# Channel_B.net
KiCad netlist of a schematic drawn in Altium Designer
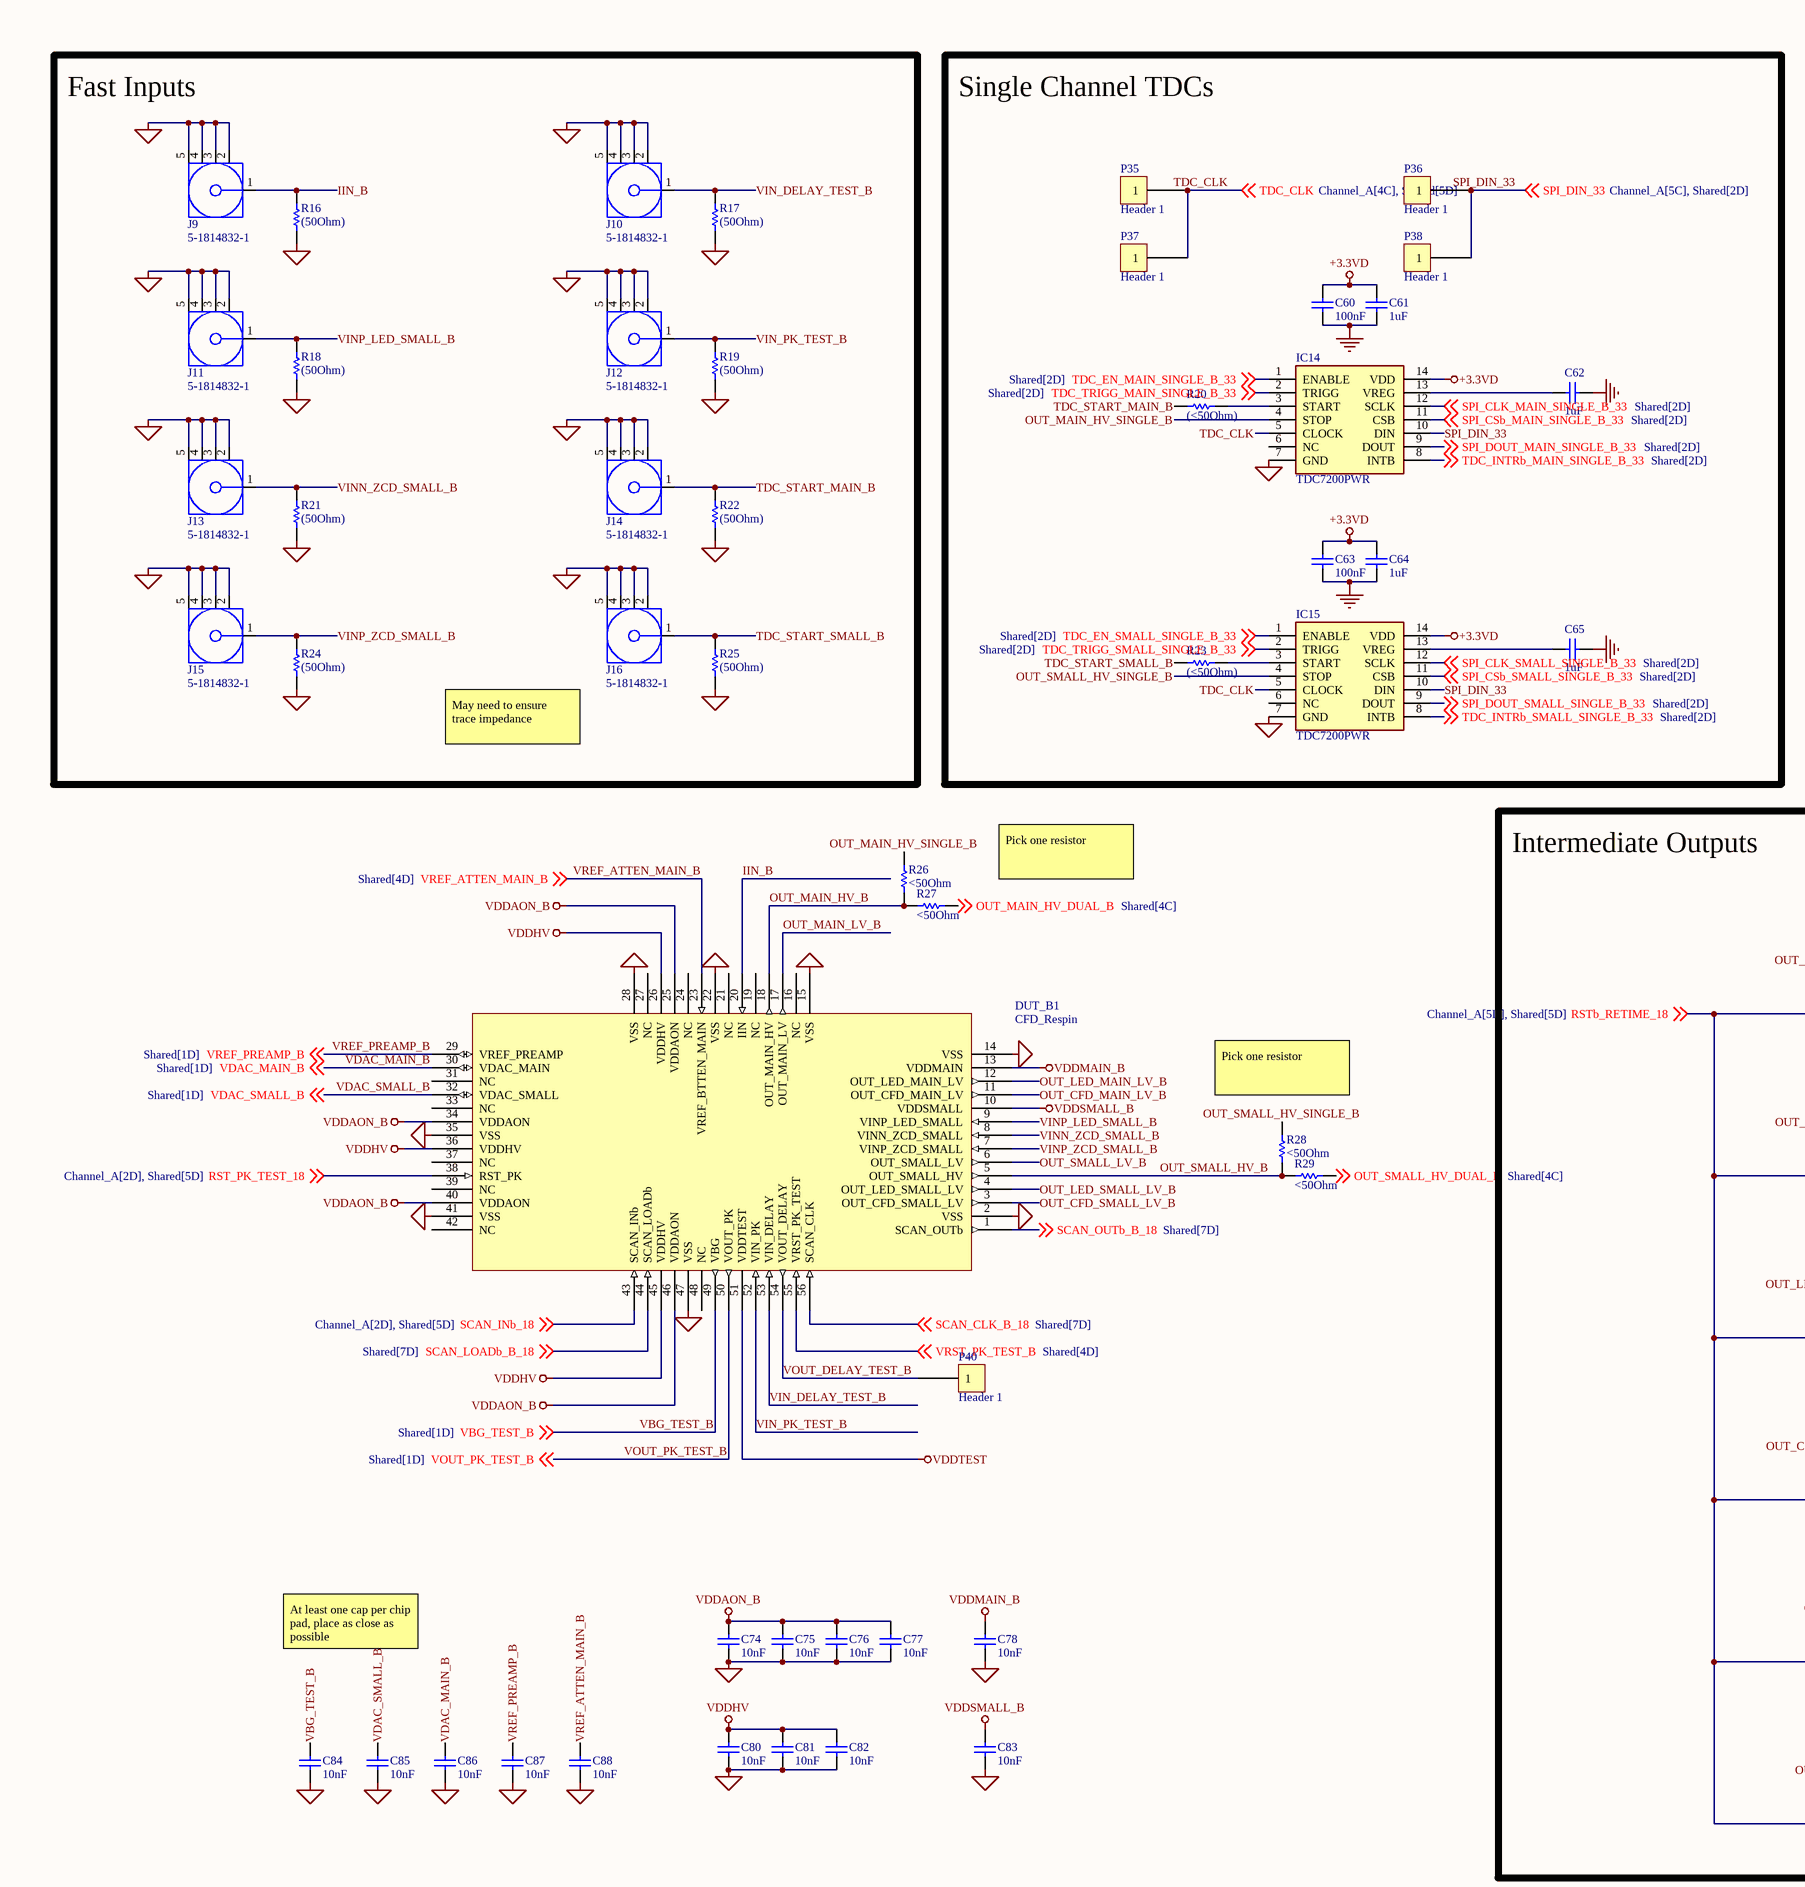
[diagram p0: Channel_B.SchDoc, left]
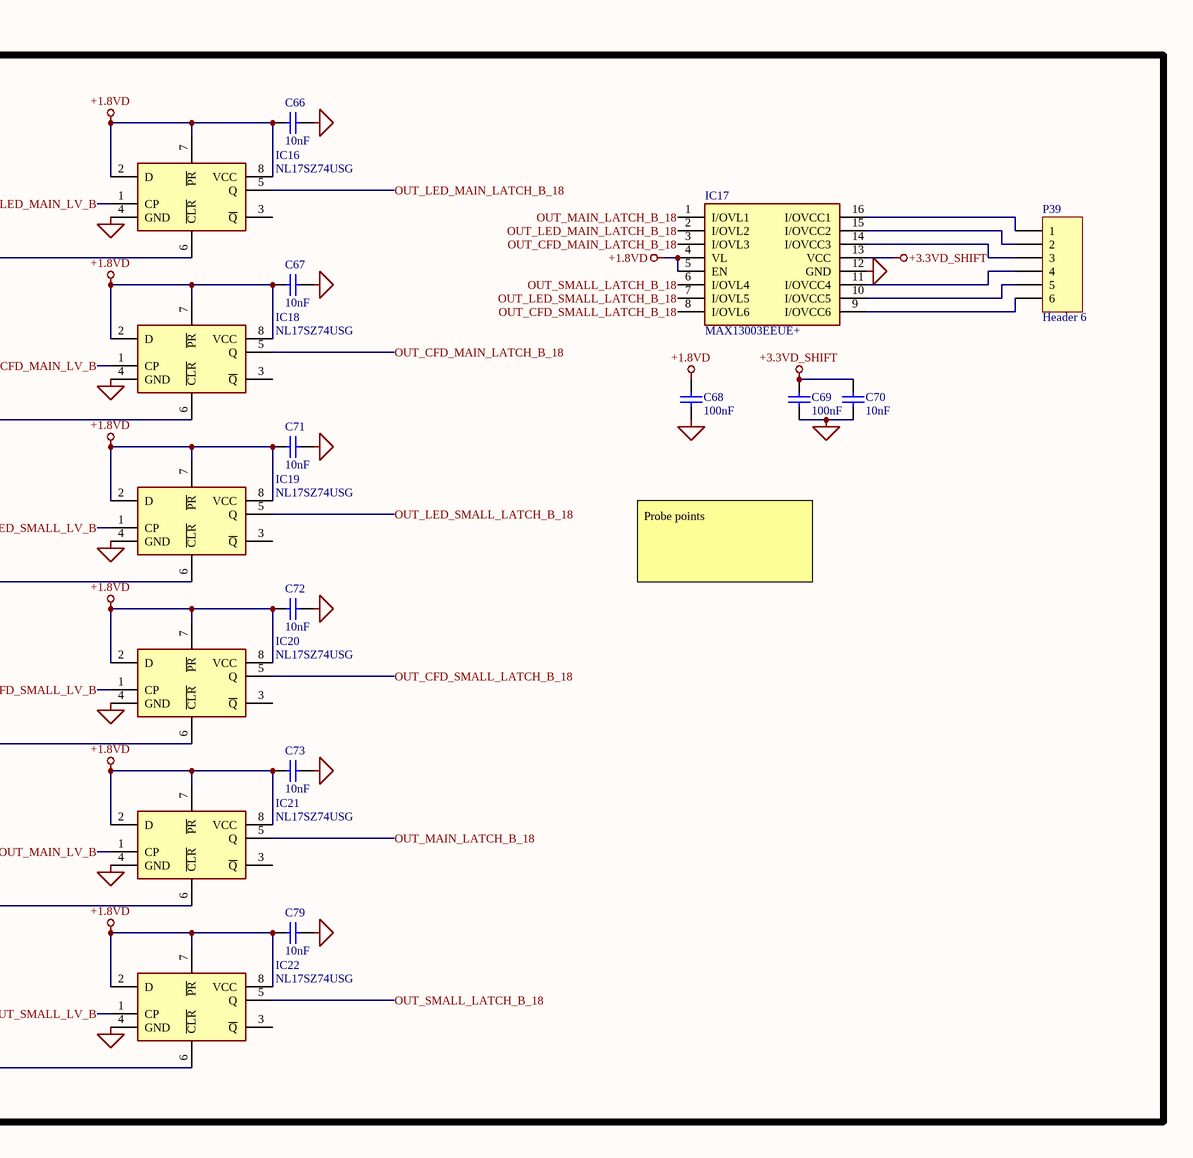
[diagram p1: Channel_B.SchDoc, right]

(export (version "E")
  (design (tool "Eeschema 10.0.6"))
  (components
    (comp (ref "C60")
      (value "100nF")
      (footprint "CAPC1608X90X35ML10T15")
      (description "0603")
      (fields (field (name "MANUFACTURER") "Murata"))
      (libsource (lib "Altium Content Vault") (part "CAP-NP-2"))
    )
    (comp (ref "C61")
      (value "1uF")
      (footprint "CAPC1608X90X35ML10T15")
      (description "0603")
      (fields (field (name "MANUFACTURER") "Murata"))
      (libsource (lib "Altium Content Vault") (part "CAP-NP-2"))
    )
    (comp (ref "C62")
      (value "1uF")
      (footprint "CAPC1608X90X35ML10T15")
      (description "0603")
      (fields (field (name "MANUFACTURER") "Murata"))
      (libsource (lib "Altium Content Vault") (part "CAP-NP-2"))
    )
    (comp (ref "C63")
      (value "100nF")
      (footprint "CAPC1608X90X35ML10T15")
      (description "0603")
      (fields (field (name "MANUFACTURER") "Murata"))
      (libsource (lib "Altium Content Vault") (part "CAP-NP-2"))
    )
    (comp (ref "C64")
      (value "1uF")
      (footprint "CAPC1608X90X35ML10T15")
      (description "0603")
      (fields (field (name "MANUFACTURER") "Murata"))
      (libsource (lib "Altium Content Vault") (part "CAP-NP-2"))
    )
    (comp (ref "C65")
      (value "1uF")
      (footprint "CAPC1608X90X35ML10T15")
      (description "0603")
      (fields (field (name "MANUFACTURER") "Murata"))
      (libsource (lib "Altium Content Vault") (part "CAP-NP-2"))
    )
    (comp (ref "C66")
      (value "10nF")
      (footprint "CAPC1608X90X35ML10T15")
      (description "0603")
      (fields (field (name "MANUFACTURER") "Murata"))
      (libsource (lib "Altium Content Vault") (part "CAP-NP-2"))
    )
    (comp (ref "C67")
      (value "10nF")
      (footprint "CAPC1608X90X35ML10T15")
      (description "0603")
      (fields (field (name "MANUFACTURER") "Murata"))
      (libsource (lib "Altium Content Vault") (part "CAP-NP-2"))
    )
    (comp (ref "C68")
      (value "100nF")
      (footprint "CAPC1608X90X35ML10T15")
      (description "0603")
      (fields (field (name "MANUFACTURER") "Murata"))
      (libsource (lib "Altium Content Vault") (part "CAP-NP-2"))
    )
    (comp (ref "C69")
      (value "100nF")
      (footprint "CAPC1608X90X35ML10T15")
      (description "0603")
      (fields (field (name "MANUFACTURER") "Murata"))
      (libsource (lib "Altium Content Vault") (part "CAP-NP-2"))
    )
    (comp (ref "C70")
      (value "10nF")
      (footprint "CAPC1608X90X35ML10T15")
      (description "0603")
      (fields (field (name "MANUFACTURER") "Murata"))
      (libsource (lib "Altium Content Vault") (part "CAP-NP-2"))
    )
    (comp (ref "C71")
      (value "10nF")
      (footprint "CAPC1608X90X35ML10T15")
      (description "0603")
      (fields (field (name "MANUFACTURER") "Murata"))
      (libsource (lib "Altium Content Vault") (part "CAP-NP-2"))
    )
    (comp (ref "C72")
      (value "10nF")
      (footprint "CAPC1608X90X35ML10T15")
      (description "0603")
      (fields (field (name "MANUFACTURER") "Murata"))
      (libsource (lib "Altium Content Vault") (part "CAP-NP-2"))
    )
    (comp (ref "C73")
      (value "10nF")
      (footprint "CAPC1608X90X35ML10T15")
      (description "0603")
      (fields (field (name "MANUFACTURER") "Murata"))
      (libsource (lib "Altium Content Vault") (part "CAP-NP-2"))
    )
    (comp (ref "C74")
      (value "10nF")
      (footprint "CAPC1608X90X35ML10T15")
      (description "0603")
      (fields (field (name "MANUFACTURER") "Murata"))
      (libsource (lib "Altium Content Vault") (part "CAP-NP-2"))
    )
    (comp (ref "C75")
      (value "10nF")
      (footprint "CAPC1608X90X35ML10T15")
      (description "0603")
      (fields (field (name "MANUFACTURER") "Murata"))
      (libsource (lib "Altium Content Vault") (part "CAP-NP-2"))
    )
    (comp (ref "C76")
      (value "10nF")
      (footprint "CAPC1608X90X35ML10T15")
      (description "0603")
      (fields (field (name "MANUFACTURER") "Murata"))
      (libsource (lib "Altium Content Vault") (part "CAP-NP-2"))
    )
    (comp (ref "C77")
      (value "10nF")
      (footprint "CAPC1608X90X35ML10T15")
      (description "0603")
      (fields (field (name "MANUFACTURER") "Murata"))
      (libsource (lib "Altium Content Vault") (part "CAP-NP-2"))
    )
    (comp (ref "C78")
      (value "10nF")
      (footprint "CAPC1608X90X35ML10T15")
      (description "0603")
      (fields (field (name "MANUFACTURER") "Murata"))
      (libsource (lib "Altium Content Vault") (part "CAP-NP-2"))
    )
    (comp (ref "C79")
      (value "10nF")
      (footprint "CAPC1608X90X35ML10T15")
      (description "0603")
      (fields (field (name "MANUFACTURER") "Murata"))
      (libsource (lib "Altium Content Vault") (part "CAP-NP-2"))
    )
    (comp (ref "C80")
      (value "10nF")
      (footprint "CAPC1608X90X35ML10T15")
      (description "0603")
      (fields (field (name "MANUFACTURER") "Murata"))
      (libsource (lib "Altium Content Vault") (part "CAP-NP-2"))
    )
    (comp (ref "C81")
      (value "10nF")
      (footprint "CAPC1608X90X35ML10T15")
      (description "0603")
      (fields (field (name "MANUFACTURER") "Murata"))
      (libsource (lib "Altium Content Vault") (part "CAP-NP-2"))
    )
    (comp (ref "C82")
      (value "10nF")
      (footprint "CAPC1608X90X35ML10T15")
      (description "0603")
      (fields (field (name "MANUFACTURER") "Murata"))
      (libsource (lib "Altium Content Vault") (part "CAP-NP-2"))
    )
    (comp (ref "C83")
      (value "10nF")
      (footprint "CAPC1608X90X35ML10T15")
      (description "0603")
      (fields (field (name "MANUFACTURER") "Murata"))
      (libsource (lib "Altium Content Vault") (part "CAP-NP-2"))
    )
    (comp (ref "C84")
      (value "10nF")
      (footprint "CAPC1608X90X35ML10T15")
      (description "0603")
      (fields (field (name "MANUFACTURER") "Murata"))
      (libsource (lib "Altium Content Vault") (part "CAP-NP-2"))
    )
    (comp (ref "C85")
      (value "10nF")
      (footprint "CAPC1608X90X35ML10T15")
      (description "0603")
      (fields (field (name "MANUFACTURER") "Murata"))
      (libsource (lib "Altium Content Vault") (part "CAP-NP-2"))
    )
    (comp (ref "C86")
      (value "10nF")
      (footprint "CAPC1608X90X35ML10T15")
      (description "0603")
      (fields (field (name "MANUFACTURER") "Murata"))
      (libsource (lib "Altium Content Vault") (part "CAP-NP-2"))
    )
    (comp (ref "C87")
      (value "10nF")
      (footprint "CAPC1608X90X35ML10T15")
      (description "0603")
      (fields (field (name "MANUFACTURER") "Murata"))
      (libsource (lib "Altium Content Vault") (part "CAP-NP-2"))
    )
    (comp (ref "C88")
      (value "10nF")
      (footprint "CAPC1608X90X35ML10T15")
      (description "0603")
      (fields (field (name "MANUFACTURER") "Murata"))
      (libsource (lib "Altium Content Vault") (part "CAP-NP-2"))
    )
    (comp (ref "DUT_B1")
      (value "CFD_Respin")
      (footprint "QFN50P800X800X80_HS-57N_WIDEVIAS")
      (libsource (lib "intlib") (part "CFD_Respin"))
    )
    (comp (ref "IC14")
      (value "TDC7200PWR")
      (footprint "SamacSys:SOP65P640X120-14N")
      (description "Integrated Circuit")
      (libsource (lib "*") (part "TDC7200PWR"))
    )
    (comp (ref "IC15")
      (value "TDC7200PWR")
      (footprint "SamacSys:SOP65P640X120-14N")
      (description "Integrated Circuit")
      (libsource (lib "*") (part "TDC7200PWR"))
    )
    (comp (ref "IC16")
      (value "NL17SZ74USG")
      (footprint "SamacSys:SOP50P310X90-8N")
      (description "Flip Flops 1.65-5.5V CMOS Single D-Type")
      (libsource (lib "SamacSys") (part "NL17SZ74USG"))
    )
    (comp (ref "IC17")
      (value "MAX13003EEUE+")
      (footprint "SamacSys:SOP65P640X110-16N")
      (description "Integrated Circuit")
      (libsource (lib "*") (part "MAX13003EEUE+"))
    )
    (comp (ref "IC18")
      (value "NL17SZ74USG")
      (footprint "SamacSys:SOP50P310X90-8N")
      (description "Flip Flops 1.65-5.5V CMOS Single D-Type")
      (libsource (lib "SamacSys") (part "NL17SZ74USG"))
    )
    (comp (ref "IC19")
      (value "NL17SZ74USG")
      (footprint "SamacSys:SOP50P310X90-8N")
      (description "Flip Flops 1.65-5.5V CMOS Single D-Type")
      (libsource (lib "SamacSys") (part "NL17SZ74USG"))
    )
    (comp (ref "IC20")
      (value "NL17SZ74USG")
      (footprint "SamacSys:SOP50P310X90-8N")
      (description "Flip Flops 1.65-5.5V CMOS Single D-Type")
      (libsource (lib "SamacSys") (part "NL17SZ74USG"))
    )
    (comp (ref "IC21")
      (value "NL17SZ74USG")
      (footprint "SamacSys:SOP50P310X90-8N")
      (description "Flip Flops 1.65-5.5V CMOS Single D-Type")
      (libsource (lib "SamacSys") (part "NL17SZ74USG"))
    )
    (comp (ref "IC22")
      (value "NL17SZ74USG")
      (footprint "SamacSys:SOP50P310X90-8N")
      (description "Flip Flops 1.65-5.5V CMOS Single D-Type")
      (libsource (lib "SamacSys") (part "NL17SZ74USG"))
    )
    (comp (ref "J9")
      (value "5-1814832-1")
      (footprint "TECO-5-1814832-1_V")
      (fields (field (name "MANUFACTURER") "TE Connectivity"))
      (libsource (lib "Altium Content Vault") (part "CN-S-4F-RF5"))
    )
    (comp (ref "J10")
      (value "5-1814832-1")
      (footprint "TECO-5-1814832-1_V")
      (fields (field (name "MANUFACTURER") "TE Connectivity"))
      (libsource (lib "Altium Content Vault") (part "CN-S-4F-RF5"))
    )
    (comp (ref "J11")
      (value "5-1814832-1")
      (footprint "TECO-5-1814832-1_V")
      (fields (field (name "MANUFACTURER") "TE Connectivity"))
      (libsource (lib "Altium Content Vault") (part "CN-S-4F-RF5"))
    )
    (comp (ref "J12")
      (value "5-1814832-1")
      (footprint "TECO-5-1814832-1_V")
      (fields (field (name "MANUFACTURER") "TE Connectivity"))
      (libsource (lib "Altium Content Vault") (part "CN-S-4F-RF5"))
    )
    (comp (ref "J13")
      (value "5-1814832-1")
      (footprint "TECO-5-1814832-1_V")
      (fields (field (name "MANUFACTURER") "TE Connectivity"))
      (libsource (lib "Altium Content Vault") (part "CN-S-4F-RF5"))
    )
    (comp (ref "J14")
      (value "5-1814832-1")
      (footprint "TECO-5-1814832-1_V")
      (fields (field (name "MANUFACTURER") "TE Connectivity"))
      (libsource (lib "Altium Content Vault") (part "CN-S-4F-RF5"))
    )
    (comp (ref "J15")
      (value "5-1814832-1")
      (footprint "TECO-5-1814832-1_V")
      (fields (field (name "MANUFACTURER") "TE Connectivity"))
      (libsource (lib "Altium Content Vault") (part "CN-S-4F-RF5"))
    )
    (comp (ref "J16")
      (value "5-1814832-1")
      (footprint "TECO-5-1814832-1_V")
      (fields (field (name "MANUFACTURER") "TE Connectivity"))
      (libsource (lib "Altium Content Vault") (part "CN-S-4F-RF5"))
    )
    (comp (ref "P35") (value "Header 1") (footprint "Header1") (libsource (lib "intlib") (part "Header 1")))
    (comp (ref "P36") (value "Header 1") (footprint "Header1") (libsource (lib "intlib") (part "Header 1")))
    (comp (ref "P37") (value "Header 1") (footprint "Header1") (libsource (lib "intlib") (part "Header 1")))
    (comp (ref "P38") (value "Header 1") (footprint "Header1") (libsource (lib "intlib") (part "Header 1")))
    (comp (ref "P39")
      (value "Header 6")
      (footprint "HDR1X6")
      (description "Header, 6-Pin")
      (fields (field (name "PUBLISHER") "Altium Limited"))
      (libsource (lib "Miscellaneous Connectors") (part "Header 6"))
    )
    (comp (ref "P40") (value "Header 1") (footprint "Header1") (libsource (lib "") (part "Header 1_1")))
    (comp (ref "R16")
      (value "(50Ohm)")
      (footprint "RESC1609X50X30NL8T20")
      (description "0603")
      (fields (field (name "MANUFACTURER") "Vishay Semiconductor"))
      (libsource (lib "Altium Content Vault") (part "RES-2"))
    )
    (comp (ref "R17")
      (value "(50Ohm)")
      (footprint "RESC1609X50X30NL8T20")
      (description "0603")
      (fields (field (name "MANUFACTURER") "Vishay Semiconductor"))
      (libsource (lib "Altium Content Vault") (part "RES-2"))
    )
    (comp (ref "R18")
      (value "(50Ohm)")
      (footprint "RESC1609X50X30NL8T20")
      (description "0603")
      (fields (field (name "MANUFACTURER") "Vishay Semiconductor"))
      (libsource (lib "Altium Content Vault") (part "RES-2"))
    )
    (comp (ref "R19")
      (value "(50Ohm)")
      (footprint "RESC1609X50X30NL8T20")
      (description "0603")
      (fields (field (name "MANUFACTURER") "Vishay Semiconductor"))
      (libsource (lib "Altium Content Vault") (part "RES-2"))
    )
    (comp (ref "R20")
      (value "(<50Ohm)")
      (footprint "RESC1609X50X30NL8T20")
      (description "0603")
      (fields (field (name "MANUFACTURER") "Vishay Semiconductor"))
      (libsource (lib "Altium Content Vault") (part "RES-2"))
    )
    (comp (ref "R21")
      (value "(50Ohm)")
      (footprint "RESC1609X50X30NL8T20")
      (description "0603")
      (fields (field (name "MANUFACTURER") "Vishay Semiconductor"))
      (libsource (lib "Altium Content Vault") (part "RES-2"))
    )
    (comp (ref "R22")
      (value "(50Ohm)")
      (footprint "RESC1609X50X30NL8T20")
      (description "0603")
      (fields (field (name "MANUFACTURER") "Vishay Semiconductor"))
      (libsource (lib "Altium Content Vault") (part "RES-2"))
    )
    (comp (ref "R23")
      (value "(<50Ohm)")
      (footprint "RESC1609X50X30NL8T20")
      (description "0603")
      (fields (field (name "MANUFACTURER") "Vishay Semiconductor"))
      (libsource (lib "Altium Content Vault") (part "RES-2"))
    )
    (comp (ref "R24")
      (value "(50Ohm)")
      (footprint "RESC1609X50X30NL8T20")
      (description "0603")
      (fields (field (name "MANUFACTURER") "Vishay Semiconductor"))
      (libsource (lib "Altium Content Vault") (part "RES-2"))
    )
    (comp (ref "R25")
      (value "(50Ohm)")
      (footprint "RESC1609X50X30NL8T20")
      (description "0603")
      (fields (field (name "MANUFACTURER") "Vishay Semiconductor"))
      (libsource (lib "Altium Content Vault") (part "RES-2"))
    )
    (comp (ref "R26")
      (value "<50Ohm")
      (footprint "RESC1609X50X30NL8T20")
      (description "0603")
      (fields (field (name "MANUFACTURER") "Vishay Semiconductor"))
      (libsource (lib "Altium Content Vault") (part "RES-2"))
    )
    (comp (ref "R27")
      (value "<50Ohm")
      (footprint "RESC1609X50X30NL8T20")
      (description "0603")
      (fields (field (name "MANUFACTURER") "Vishay Semiconductor"))
      (libsource (lib "Altium Content Vault") (part "RES-2"))
    )
    (comp (ref "R28")
      (value "<50Ohm")
      (footprint "RESC1609X50X30NL8T20")
      (description "0603")
      (fields (field (name "MANUFACTURER") "Vishay Semiconductor"))
      (libsource (lib "Altium Content Vault") (part "RES-2"))
    )
    (comp (ref "R29")
      (value "<50Ohm")
      (footprint "RESC1609X50X30NL8T20")
      (description "0603")
      (fields (field (name "MANUFACTURER") "Vishay Semiconductor"))
      (libsource (lib "Altium Content Vault") (part "RES-2"))
    )
  )
  (nets
    (net (code "1") (name "+1.8VD") (class "Default")
      (node (ref "C66") (pin "2") (pinfunction "2_2") (pintype "passive"))
      (node (ref "C67") (pin "2") (pinfunction "2_2") (pintype "passive"))
      (node (ref "C68") (pin "2") (pinfunction "2_2") (pintype "passive"))
      (node (ref "C71") (pin "2") (pinfunction "2_2") (pintype "passive"))
      (node (ref "C72") (pin "2") (pinfunction "2_2") (pintype "passive"))
      (node (ref "C73") (pin "2") (pinfunction "2_2") (pintype "passive"))
      (node (ref "C79") (pin "2") (pinfunction "2_2") (pintype "passive"))
      (node (ref "IC16") (pin "2") (pinfunction "D_2") (pintype "passive"))
      (node (ref "IC16") (pin "7") (pinfunction "~{PR}_7") (pintype "passive"))
      (node (ref "IC16") (pin "8") (pinfunction "VCC_8") (pintype "passive"))
      (node (ref "IC17") (pin "4") (pinfunction "VL_4") (pintype "passive"))
      (node (ref "IC17") (pin "5") (pinfunction "EN_5") (pintype "passive"))
      (node (ref "IC18") (pin "2") (pinfunction "D_2") (pintype "passive"))
      (node (ref "IC18") (pin "7") (pinfunction "~{PR}_7") (pintype "passive"))
      (node (ref "IC18") (pin "8") (pinfunction "VCC_8") (pintype "passive"))
      (node (ref "IC19") (pin "2") (pinfunction "D_2") (pintype "passive"))
      (node (ref "IC19") (pin "7") (pinfunction "~{PR}_7") (pintype "passive"))
      (node (ref "IC19") (pin "8") (pinfunction "VCC_8") (pintype "passive"))
      (node (ref "IC20") (pin "2") (pinfunction "D_2") (pintype "passive"))
      (node (ref "IC20") (pin "7") (pinfunction "~{PR}_7") (pintype "passive"))
      (node (ref "IC20") (pin "8") (pinfunction "VCC_8") (pintype "passive"))
      (node (ref "IC21") (pin "2") (pinfunction "D_2") (pintype "passive"))
      (node (ref "IC21") (pin "7") (pinfunction "~{PR}_7") (pintype "passive"))
      (node (ref "IC21") (pin "8") (pinfunction "VCC_8") (pintype "passive"))
      (node (ref "IC22") (pin "2") (pinfunction "D_2") (pintype "passive"))
      (node (ref "IC22") (pin "7") (pinfunction "~{PR}_7") (pintype "passive"))
      (node (ref "IC22") (pin "8") (pinfunction "VCC_8") (pintype "passive"))
    )
    (net (code "2") (name "+3.3VD") (class "Default")
      (node (ref "C60") (pin "1") (pinfunction "1_1") (pintype "passive"))
      (node (ref "C61") (pin "1") (pinfunction "1_1") (pintype "passive"))
      (node (ref "C63") (pin "1") (pinfunction "1_1") (pintype "passive"))
      (node (ref "C64") (pin "1") (pinfunction "1_1") (pintype "passive"))
      (node (ref "IC14") (pin "14") (pinfunction "VDD_14") (pintype "passive"))
      (node (ref "IC15") (pin "14") (pinfunction "VDD_14") (pintype "passive"))
    )
    (net (code "3") (name "+3.3VD_SHIFT") (class "Default")
      (node (ref "C69") (pin "2") (pinfunction "2_2") (pintype "passive"))
      (node (ref "C70") (pin "2") (pinfunction "2_2") (pintype "passive"))
      (node (ref "IC17") (pin "13") (pinfunction "VCC_13") (pintype "passive"))
    )
    (net (code "4") (name "/IIN_B") (class "Default")
      (node (ref "DUT_B1") (pin "20") (pinfunction "IIN_20") (pintype "input"))
      (node (ref "J9") (pin "1") (pinfunction "1_1") (pintype "passive"))
      (node (ref "R16") (pin "2") (pinfunction "2_2") (pintype "passive"))
    )
    (net (code "5") (name "/OUT_CFD_MAIN_LATCH_B_18") (class "Default")
      (node (ref "IC17") (pin "3") (pinfunction "I/OVL3_3") (pintype "passive"))
      (node (ref "IC18") (pin "5") (pinfunction "Q_5") (pintype "passive"))
    )
    (net (code "6") (name "/OUT_CFD_MAIN_LV_B") (class "Default")
      (node (ref "DUT_B1") (pin "11") (pinfunction "OUT_CFD_MAIN_LV_11") (pintype "output"))
      (node (ref "IC18") (pin "1") (pinfunction "CP_1") (pintype "passive"))
    )
    (net (code "7") (name "/OUT_CFD_SMALL_LATCH_B_18") (class "Default")
      (node (ref "IC17") (pin "8") (pinfunction "I/OVL6_8") (pintype "passive"))
      (node (ref "IC20") (pin "5") (pinfunction "Q_5") (pintype "passive"))
    )
    (net (code "8") (name "/OUT_CFD_SMALL_LV_B") (class "Default")
      (node (ref "DUT_B1") (pin "3") (pinfunction "OUT_CFD_SMALL_LV_3") (pintype "output"))
      (node (ref "IC20") (pin "1") (pinfunction "CP_1") (pintype "passive"))
    )
    (net (code "9") (name "/OUT_LED_MAIN_LATCH_B_18") (class "Default")
      (node (ref "IC16") (pin "5") (pinfunction "Q_5") (pintype "passive"))
      (node (ref "IC17") (pin "2") (pinfunction "I/OVL2_2") (pintype "passive"))
    )
    (net (code "10") (name "/OUT_LED_MAIN_LV_B") (class "Default")
      (node (ref "DUT_B1") (pin "12") (pinfunction "OUT_LED_MAIN_LV_12") (pintype "output"))
      (node (ref "IC16") (pin "1") (pinfunction "CP_1") (pintype "passive"))
    )
    (net (code "11") (name "/OUT_LED_SMALL_LATCH_B_18") (class "Default")
      (node (ref "IC17") (pin "7") (pinfunction "I/OVL5_7") (pintype "passive"))
      (node (ref "IC19") (pin "5") (pinfunction "Q_5") (pintype "passive"))
    )
    (net (code "12") (name "/OUT_LED_SMALL_LV_B") (class "Default")
      (node (ref "DUT_B1") (pin "4") (pinfunction "OUT_LED_SMALL_LV_4") (pintype "output"))
      (node (ref "IC19") (pin "1") (pinfunction "CP_1") (pintype "passive"))
    )
    (net (code "13") (name "/OUT_MAIN_HV_B") (class "Default")
      (node (ref "DUT_B1") (pin "18") (pinfunction "OUT_MAIN_HV_18") (pintype "output"))
      (node (ref "R26") (pin "2") (pinfunction "2_2") (pintype "passive"))
      (node (ref "R27") (pin "1") (pinfunction "1_1") (pintype "passive"))
    )
    (net (code "14") (name "/OUT_MAIN_HV_SINGLE_B") (class "Default")
      (node (ref "IC14") (pin "4") (pinfunction "STOP_4") (pintype "passive"))
      (node (ref "R26") (pin "1") (pinfunction "1_1") (pintype "passive"))
    )
    (net (code "15") (name "/OUT_MAIN_LATCH_B_18") (class "Default")
      (node (ref "IC17") (pin "1") (pinfunction "I/OVL1_1") (pintype "passive"))
      (node (ref "IC21") (pin "5") (pinfunction "Q_5") (pintype "passive"))
    )
    (net (code "16") (name "/OUT_MAIN_LV_B") (class "Default")
      (node (ref "DUT_B1") (pin "17") (pinfunction "OUT_MAIN_LV_17") (pintype "output"))
      (node (ref "IC21") (pin "1") (pinfunction "CP_1") (pintype "passive"))
    )
    (net (code "17") (name "/OUT_SMALL_HV_B") (class "Default")
      (node (ref "DUT_B1") (pin "5") (pinfunction "OUT_SMALL_HV_5") (pintype "output"))
      (node (ref "R28") (pin "2") (pinfunction "2_2") (pintype "passive"))
      (node (ref "R29") (pin "1") (pinfunction "1_1") (pintype "passive"))
    )
    (net (code "18") (name "/OUT_SMALL_HV_SINGLE_B") (class "Default")
      (node (ref "IC15") (pin "4") (pinfunction "STOP_4") (pintype "passive"))
      (node (ref "R28") (pin "1") (pinfunction "1_1") (pintype "passive"))
    )
    (net (code "19") (name "/OUT_SMALL_LATCH_B_18") (class "Default")
      (node (ref "IC17") (pin "6") (pinfunction "I/OVL4_6") (pintype "passive"))
      (node (ref "IC22") (pin "5") (pinfunction "Q_5") (pintype "passive"))
    )
    (net (code "20") (name "/OUT_SMALL_LV_B") (class "Default")
      (node (ref "DUT_B1") (pin "6") (pinfunction "OUT_SMALL_LV_6") (pintype "output"))
      (node (ref "IC22") (pin "1") (pinfunction "CP_1") (pintype "passive"))
    )
    (net (code "21") (name "/TDC_START_MAIN_B") (class "Default")
      (node (ref "J14") (pin "1") (pinfunction "1_1") (pintype "passive"))
      (node (ref "R20") (pin "1") (pinfunction "1_1") (pintype "passive"))
      (node (ref "R22") (pin "2") (pinfunction "2_2") (pintype "passive"))
    )
    (net (code "22") (name "/TDC_START_SMALL_B") (class "Default")
      (node (ref "J16") (pin "1") (pinfunction "1_1") (pintype "passive"))
      (node (ref "R23") (pin "1") (pinfunction "1_1") (pintype "passive"))
      (node (ref "R25") (pin "2") (pinfunction "2_2") (pintype "passive"))
    )
    (net (code "23") (name "/VINN_ZCD_SMALL_B") (class "Default")
      (node (ref "DUT_B1") (pin "8") (pinfunction "VINN_ZCD_SMALL_8") (pintype "input"))
      (node (ref "J13") (pin "1") (pinfunction "1_1") (pintype "passive"))
      (node (ref "R21") (pin "2") (pinfunction "2_2") (pintype "passive"))
    )
    (net (code "24") (name "/VINP_LED_SMALL_B") (class "Default")
      (node (ref "DUT_B1") (pin "9") (pinfunction "VINP_LED_SMALL_9") (pintype "input"))
      (node (ref "J11") (pin "1") (pinfunction "1_1") (pintype "passive"))
      (node (ref "R18") (pin "2") (pinfunction "2_2") (pintype "passive"))
    )
    (net (code "25") (name "/VINP_ZCD_SMALL_B") (class "Default")
      (node (ref "DUT_B1") (pin "7") (pinfunction "VINP_ZCD_SMALL_7") (pintype "input"))
      (node (ref "J15") (pin "1") (pinfunction "1_1") (pintype "passive"))
      (node (ref "R24") (pin "2") (pinfunction "2_2") (pintype "passive"))
    )
    (net (code "26") (name "/VIN_DELAY_TEST_B") (class "Default")
      (node (ref "DUT_B1") (pin "53") (pinfunction "VIN_DELAY_53") (pintype "input"))
      (node (ref "J10") (pin "1") (pinfunction "1_1") (pintype "passive"))
      (node (ref "R17") (pin "2") (pinfunction "2_2") (pintype "passive"))
    )
    (net (code "27") (name "/VIN_PK_TEST_B") (class "Default")
      (node (ref "DUT_B1") (pin "52") (pinfunction "VIN_PK_52") (pintype "input"))
      (node (ref "J12") (pin "1") (pinfunction "1_1") (pintype "passive"))
      (node (ref "R19") (pin "2") (pinfunction "2_2") (pintype "passive"))
    )
    (net (code "28") (name "/VOUT_DELAY_TEST_B") (class "Default")
      (node (ref "DUT_B1") (pin "54") (pinfunction "VOUT_DELAY_54") (pintype "output"))
      (node (ref "P40") (pin "1") (pinfunction "1_1") (pintype "passive"))
    )
    (net (code "29") (name "GND") (class "Default")
      (node (ref "C60") (pin "2") (pinfunction "2_2") (pintype "passive"))
      (node (ref "C61") (pin "2") (pinfunction "2_2") (pintype "passive"))
      (node (ref "C62") (pin "2") (pinfunction "2_2") (pintype "passive"))
      (node (ref "C63") (pin "2") (pinfunction "2_2") (pintype "passive"))
      (node (ref "C64") (pin "2") (pinfunction "2_2") (pintype "passive"))
      (node (ref "C65") (pin "2") (pinfunction "2_2") (pintype "passive"))
      (node (ref "C66") (pin "1") (pinfunction "1_1") (pintype "passive"))
      (node (ref "C67") (pin "1") (pinfunction "1_1") (pintype "passive"))
      (node (ref "C68") (pin "1") (pinfunction "1_1") (pintype "passive"))
      (node (ref "C69") (pin "1") (pinfunction "1_1") (pintype "passive"))
      (node (ref "C70") (pin "1") (pinfunction "1_1") (pintype "passive"))
      (node (ref "C71") (pin "1") (pinfunction "1_1") (pintype "passive"))
      (node (ref "C72") (pin "1") (pinfunction "1_1") (pintype "passive"))
      (node (ref "C73") (pin "1") (pinfunction "1_1") (pintype "passive"))
      (node (ref "C74") (pin "1") (pinfunction "1_1") (pintype "passive"))
      (node (ref "C75") (pin "1") (pinfunction "1_1") (pintype "passive"))
      (node (ref "C76") (pin "1") (pinfunction "1_1") (pintype "passive"))
      (node (ref "C77") (pin "1") (pinfunction "1_1") (pintype "passive"))
      (node (ref "C78") (pin "1") (pinfunction "1_1") (pintype "passive"))
      (node (ref "C79") (pin "1") (pinfunction "1_1") (pintype "passive"))
      (node (ref "C80") (pin "1") (pinfunction "1_1") (pintype "passive"))
      (node (ref "C81") (pin "1") (pinfunction "1_1") (pintype "passive"))
      (node (ref "C82") (pin "1") (pinfunction "1_1") (pintype "passive"))
      (node (ref "C83") (pin "1") (pinfunction "1_1") (pintype "passive"))
      (node (ref "C84") (pin "1") (pinfunction "1_1") (pintype "passive"))
      (node (ref "C85") (pin "1") (pinfunction "1_1") (pintype "passive"))
      (node (ref "C86") (pin "1") (pinfunction "1_1") (pintype "passive"))
      (node (ref "C87") (pin "1") (pinfunction "1_1") (pintype "passive"))
      (node (ref "C88") (pin "1") (pinfunction "1_1") (pintype "passive"))
      (node (ref "DUT_B1") (pin "14") (pinfunction "VSS_14") (pintype "power_in"))
      (node (ref "DUT_B1") (pin "15") (pinfunction "VSS_15") (pintype "power_in"))
      (node (ref "DUT_B1") (pin "2") (pinfunction "VSS_2") (pintype "power_in"))
      (node (ref "DUT_B1") (pin "22") (pinfunction "VSS_22") (pintype "power_in"))
      (node (ref "DUT_B1") (pin "28") (pinfunction "VSS_28") (pintype "power_in"))
      (node (ref "DUT_B1") (pin "35") (pinfunction "VSS_35") (pintype "power_in"))
      (node (ref "DUT_B1") (pin "41") (pinfunction "VSS_41") (pintype "power_in"))
      (node (ref "DUT_B1") (pin "47") (pinfunction "VSS_47") (pintype "power_in"))
      (node (ref "IC14") (pin "7") (pinfunction "GND_7") (pintype "passive"))
      (node (ref "IC15") (pin "7") (pinfunction "GND_7") (pintype "passive"))
      (node (ref "IC16") (pin "4") (pinfunction "GND_4") (pintype "passive"))
      (node (ref "IC17") (pin "12") (pinfunction "GND_12") (pintype "passive"))
      (node (ref "IC18") (pin "4") (pinfunction "GND_4") (pintype "passive"))
      (node (ref "IC19") (pin "4") (pinfunction "GND_4") (pintype "passive"))
      (node (ref "IC20") (pin "4") (pinfunction "GND_4") (pintype "passive"))
      (node (ref "IC21") (pin "4") (pinfunction "GND_4") (pintype "passive"))
      (node (ref "IC22") (pin "4") (pinfunction "GND_4") (pintype "passive"))
      (node (ref "J10") (pin "2") (pinfunction "2_2") (pintype "passive"))
      (node (ref "J10") (pin "3") (pinfunction "3_3") (pintype "passive"))
      (node (ref "J10") (pin "4") (pinfunction "4_4") (pintype "passive"))
      (node (ref "J10") (pin "5") (pinfunction "5_5") (pintype "passive"))
      (node (ref "J11") (pin "2") (pinfunction "2_2") (pintype "passive"))
      (node (ref "J11") (pin "3") (pinfunction "3_3") (pintype "passive"))
      (node (ref "J11") (pin "4") (pinfunction "4_4") (pintype "passive"))
      (node (ref "J11") (pin "5") (pinfunction "5_5") (pintype "passive"))
      (node (ref "J12") (pin "2") (pinfunction "2_2") (pintype "passive"))
      (node (ref "J12") (pin "3") (pinfunction "3_3") (pintype "passive"))
      (node (ref "J12") (pin "4") (pinfunction "4_4") (pintype "passive"))
      (node (ref "J12") (pin "5") (pinfunction "5_5") (pintype "passive"))
      (node (ref "J13") (pin "2") (pinfunction "2_2") (pintype "passive"))
      (node (ref "J13") (pin "3") (pinfunction "3_3") (pintype "passive"))
      (node (ref "J13") (pin "4") (pinfunction "4_4") (pintype "passive"))
      (node (ref "J13") (pin "5") (pinfunction "5_5") (pintype "passive"))
      (node (ref "J14") (pin "2") (pinfunction "2_2") (pintype "passive"))
      (node (ref "J14") (pin "3") (pinfunction "3_3") (pintype "passive"))
      (node (ref "J14") (pin "4") (pinfunction "4_4") (pintype "passive"))
      (node (ref "J14") (pin "5") (pinfunction "5_5") (pintype "passive"))
      (node (ref "J15") (pin "2") (pinfunction "2_2") (pintype "passive"))
      (node (ref "J15") (pin "3") (pinfunction "3_3") (pintype "passive"))
      (node (ref "J15") (pin "4") (pinfunction "4_4") (pintype "passive"))
      (node (ref "J15") (pin "5") (pinfunction "5_5") (pintype "passive"))
      (node (ref "J16") (pin "2") (pinfunction "2_2") (pintype "passive"))
      (node (ref "J16") (pin "3") (pinfunction "3_3") (pintype "passive"))
      (node (ref "J16") (pin "4") (pinfunction "4_4") (pintype "passive"))
      (node (ref "J16") (pin "5") (pinfunction "5_5") (pintype "passive"))
      (node (ref "J9") (pin "2") (pinfunction "2_2") (pintype "passive"))
      (node (ref "J9") (pin "3") (pinfunction "3_3") (pintype "passive"))
      (node (ref "J9") (pin "4") (pinfunction "4_4") (pintype "passive"))
      (node (ref "J9") (pin "5") (pinfunction "5_5") (pintype "passive"))
      (node (ref "R16") (pin "1") (pinfunction "1_1") (pintype "passive"))
      (node (ref "R17") (pin "1") (pinfunction "1_1") (pintype "passive"))
      (node (ref "R18") (pin "1") (pinfunction "1_1") (pintype "passive"))
      (node (ref "R19") (pin "1") (pinfunction "1_1") (pintype "passive"))
      (node (ref "R21") (pin "1") (pinfunction "1_1") (pintype "passive"))
      (node (ref "R22") (pin "1") (pinfunction "1_1") (pintype "passive"))
      (node (ref "R24") (pin "1") (pinfunction "1_1") (pintype "passive"))
      (node (ref "R25") (pin "1") (pinfunction "1_1") (pintype "passive"))
    )
    (net (code "30") (name "Net-(IC14-START)") (class "Default")
      (node (ref "IC14") (pin "3") (pinfunction "START_3") (pintype "passive"))
      (node (ref "R20") (pin "2") (pinfunction "2_2") (pintype "passive"))
    )
    (net (code "31") (name "Net-(IC14-VREG)") (class "Default")
      (node (ref "C62") (pin "1") (pinfunction "1_1") (pintype "passive"))
      (node (ref "IC14") (pin "13") (pinfunction "VREG_13") (pintype "passive"))
    )
    (net (code "32") (name "Net-(IC15-START)") (class "Default")
      (node (ref "IC15") (pin "3") (pinfunction "START_3") (pintype "passive"))
      (node (ref "R23") (pin "2") (pinfunction "2_2") (pintype "passive"))
    )
    (net (code "33") (name "Net-(IC15-VREG)") (class "Default")
      (node (ref "C65") (pin "1") (pinfunction "1_1") (pintype "passive"))
      (node (ref "IC15") (pin "13") (pinfunction "VREG_13") (pintype "passive"))
    )
    (net (code "34") (name "Net-(IC17-I{slash}OVCC1)") (class "Default")
      (node (ref "IC17") (pin "16") (pinfunction "I/OVCC1_16") (pintype "passive"))
      (node (ref "P39") (pin "1") (pinfunction "1_1") (pintype "passive"))
    )
    (net (code "35") (name "Net-(IC17-I{slash}OVCC2)") (class "Default")
      (node (ref "IC17") (pin "15") (pinfunction "I/OVCC2_15") (pintype "passive"))
      (node (ref "P39") (pin "2") (pinfunction "2_2") (pintype "passive"))
    )
    (net (code "36") (name "Net-(IC17-I{slash}OVCC3)") (class "Default")
      (node (ref "IC17") (pin "14") (pinfunction "I/OVCC3_14") (pintype "passive"))
      (node (ref "P39") (pin "3") (pinfunction "3_3") (pintype "passive"))
    )
    (net (code "37") (name "Net-(IC17-I{slash}OVCC4)") (class "Default")
      (node (ref "IC17") (pin "11") (pinfunction "I/OVCC4_11") (pintype "passive"))
      (node (ref "P39") (pin "4") (pinfunction "4_4") (pintype "passive"))
    )
    (net (code "38") (name "Net-(IC17-I{slash}OVCC5)") (class "Default")
      (node (ref "IC17") (pin "10") (pinfunction "I/OVCC5_10") (pintype "passive"))
      (node (ref "P39") (pin "5") (pinfunction "5_5") (pintype "passive"))
    )
    (net (code "39") (name "Net-(IC17-I{slash}OVCC6)") (class "Default")
      (node (ref "IC17") (pin "9") (pinfunction "I/OVCC6_9") (pintype "passive"))
      (node (ref "P39") (pin "6") (pinfunction "6_6") (pintype "passive"))
    )
    (net (code "40") (name "OUT_MAIN_HV_DUAL_B") (class "Default")
      (node (ref "R27") (pin "2") (pinfunction "2_2") (pintype "passive"))
    )
    (net (code "41") (name "OUT_SMALL_HV_DUAL_B") (class "Default")
      (node (ref "R29") (pin "2") (pinfunction "2_2") (pintype "passive"))
    )
    (net (code "42") (name "RST_PK_TEST_18") (class "Default")
      (node (ref "DUT_B1") (pin "38") (pinfunction "RST_PK_38") (pintype "input"))
    )
    (net (code "43") (name "RSTb_RETIME_18") (class "Default")
      (node (ref "IC16") (pin "6") (pinfunction "~{CLR}_6") (pintype "passive"))
      (node (ref "IC18") (pin "6") (pinfunction "~{CLR}_6") (pintype "passive"))
      (node (ref "IC19") (pin "6") (pinfunction "~{CLR}_6") (pintype "passive"))
      (node (ref "IC20") (pin "6") (pinfunction "~{CLR}_6") (pintype "passive"))
      (node (ref "IC21") (pin "6") (pinfunction "~{CLR}_6") (pintype "passive"))
      (node (ref "IC22") (pin "6") (pinfunction "~{CLR}_6") (pintype "passive"))
    )
    (net (code "44") (name "SCAN_CLK_B_18") (class "Default")
      (node (ref "DUT_B1") (pin "56") (pinfunction "SCAN_CLK_56") (pintype "input"))
    )
    (net (code "45") (name "SCAN_INb_18") (class "Default")
      (node (ref "DUT_B1") (pin "43") (pinfunction "SCAN_INb_43") (pintype "input"))
    )
    (net (code "46") (name "SCAN_LOADb_B_18") (class "Default")
      (node (ref "DUT_B1") (pin "44") (pinfunction "SCAN_LOADb_44") (pintype "input"))
    )
    (net (code "47") (name "SCAN_OUTb_B_18") (class "Default")
      (node (ref "DUT_B1") (pin "1") (pinfunction "SCAN_OUTb_1") (pintype "output"))
    )
    (net (code "48") (name "SPI_CLK_MAIN_SINGLE_B_33") (class "Default")
      (node (ref "IC14") (pin "12") (pinfunction "SCLK_12") (pintype "passive"))
    )
    (net (code "49") (name "SPI_CLK_SMALL_SINGLE_B_33") (class "Default")
      (node (ref "IC15") (pin "12") (pinfunction "SCLK_12") (pintype "passive"))
    )
    (net (code "50") (name "SPI_CSb_MAIN_SINGLE_B_33") (class "Default")
      (node (ref "IC14") (pin "11") (pinfunction "CSB_11") (pintype "passive"))
    )
    (net (code "51") (name "SPI_CSb_SMALL_SINGLE_B_33") (class "Default")
      (node (ref "IC15") (pin "11") (pinfunction "CSB_11") (pintype "passive"))
    )
    (net (code "52") (name "SPI_DIN_33") (class "Default")
      (node (ref "IC14") (pin "10") (pinfunction "DIN_10") (pintype "passive"))
      (node (ref "IC15") (pin "10") (pinfunction "DIN_10") (pintype "passive"))
      (node (ref "P36") (pin "1") (pinfunction "1_1") (pintype "passive"))
      (node (ref "P38") (pin "1") (pinfunction "1_1") (pintype "passive"))
    )
    (net (code "53") (name "SPI_DOUT_MAIN_SINGLE_B_33") (class "Default")
      (node (ref "IC14") (pin "9") (pinfunction "DOUT_9") (pintype "passive"))
    )
    (net (code "54") (name "SPI_DOUT_SMALL_SINGLE_B_33") (class "Default")
      (node (ref "IC15") (pin "9") (pinfunction "DOUT_9") (pintype "passive"))
    )
    (net (code "55") (name "TDC_CLK") (class "Default")
      (node (ref "IC14") (pin "5") (pinfunction "CLOCK_5") (pintype "passive"))
      (node (ref "IC15") (pin "5") (pinfunction "CLOCK_5") (pintype "passive"))
      (node (ref "P35") (pin "1") (pinfunction "1_1") (pintype "passive"))
      (node (ref "P37") (pin "1") (pinfunction "1_1") (pintype "passive"))
    )
    (net (code "56") (name "TDC_EN_MAIN_SINGLE_B_33") (class "Default")
      (node (ref "IC14") (pin "1") (pinfunction "ENABLE_1") (pintype "passive"))
    )
    (net (code "57") (name "TDC_EN_SMALL_SINGLE_B_33") (class "Default")
      (node (ref "IC15") (pin "1") (pinfunction "ENABLE_1") (pintype "passive"))
    )
    (net (code "58") (name "TDC_INTRb_MAIN_SINGLE_B_33") (class "Default")
      (node (ref "IC14") (pin "8") (pinfunction "INTB_8") (pintype "passive"))
    )
    (net (code "59") (name "TDC_INTRb_SMALL_SINGLE_B_33") (class "Default")
      (node (ref "IC15") (pin "8") (pinfunction "INTB_8") (pintype "passive"))
    )
    (net (code "60") (name "TDC_TRIGG_MAIN_SINGLE_B_33") (class "Default")
      (node (ref "IC14") (pin "2") (pinfunction "TRIGG_2") (pintype "passive"))
    )
    (net (code "61") (name "TDC_TRIGG_SMALL_SINGLE_B_33") (class "Default")
      (node (ref "IC15") (pin "2") (pinfunction "TRIGG_2") (pintype "passive"))
    )
    (net (code "62") (name "VBG_TEST_B") (class "Default")
      (node (ref "C84") (pin "2") (pinfunction "2_2") (pintype "passive"))
      (node (ref "DUT_B1") (pin "49") (pinfunction "VBG_49") (pintype "output"))
    )
    (net (code "63") (name "VDAC_MAIN_B") (class "Default")
      (node (ref "C86") (pin "2") (pinfunction "2_2") (pintype "passive"))
      (node (ref "DUT_B1") (pin "30") (pinfunction "VDAC_MAIN_30") (pintype "bidirectional"))
    )
    (net (code "64") (name "VDAC_SMALL_B") (class "Default")
      (node (ref "C85") (pin "2") (pinfunction "2_2") (pintype "passive"))
      (node (ref "DUT_B1") (pin "32") (pinfunction "VDAC_SMALL_32") (pintype "bidirectional"))
    )
    (net (code "65") (name "VDDAON_B") (class "Default")
      (node (ref "C74") (pin "2") (pinfunction "2_2") (pintype "passive"))
      (node (ref "C75") (pin "2") (pinfunction "2_2") (pintype "passive"))
      (node (ref "C76") (pin "2") (pinfunction "2_2") (pintype "passive"))
      (node (ref "C77") (pin "2") (pinfunction "2_2") (pintype "passive"))
      (node (ref "DUT_B1") (pin "25") (pinfunction "VDDAON_25") (pintype "power_in"))
      (node (ref "DUT_B1") (pin "34") (pinfunction "VDDAON_34") (pintype "power_in"))
      (node (ref "DUT_B1") (pin "40") (pinfunction "VDDAON_40") (pintype "power_in"))
      (node (ref "DUT_B1") (pin "46") (pinfunction "VDDAON_46") (pintype "power_in"))
    )
    (net (code "66") (name "VDDHV") (class "Default")
      (node (ref "C80") (pin "2") (pinfunction "2_2") (pintype "passive"))
      (node (ref "C81") (pin "2") (pinfunction "2_2") (pintype "passive"))
      (node (ref "C82") (pin "2") (pinfunction "2_2") (pintype "passive"))
      (node (ref "DUT_B1") (pin "26") (pinfunction "VDDHV_26") (pintype "power_in"))
      (node (ref "DUT_B1") (pin "36") (pinfunction "VDDHV_36") (pintype "power_in"))
      (node (ref "DUT_B1") (pin "45") (pinfunction "VDDHV_45") (pintype "power_in"))
    )
    (net (code "67") (name "VDDMAIN_B") (class "Default")
      (node (ref "C78") (pin "2") (pinfunction "2_2") (pintype "passive"))
      (node (ref "DUT_B1") (pin "13") (pinfunction "VDDMAIN_13") (pintype "power_in"))
    )
    (net (code "68") (name "VDDSMALL_B") (class "Default")
      (node (ref "C83") (pin "2") (pinfunction "2_2") (pintype "passive"))
      (node (ref "DUT_B1") (pin "10") (pinfunction "VDDSMALL_10") (pintype "power_in"))
    )
    (net (code "69") (name "VDDTEST") (class "Default")
      (node (ref "DUT_B1") (pin "51") (pinfunction "VDDTEST_51") (pintype "power_in"))
    )
    (net (code "70") (name "VOUT_PK_TEST_B") (class "Default")
      (node (ref "DUT_B1") (pin "50") (pinfunction "VOUT_PK_50") (pintype "output"))
    )
    (net (code "71") (name "VREF_ATTEN_MAIN_B") (class "Default")
      (node (ref "C88") (pin "2") (pinfunction "2_2") (pintype "passive"))
      (node (ref "DUT_B1") (pin "23") (pinfunction "VREF_BTTEN_MAIN_23") (pintype "input"))
    )
    (net (code "72") (name "VREF_PREAMP_B") (class "Default")
      (node (ref "C87") (pin "2") (pinfunction "2_2") (pintype "passive"))
      (node (ref "DUT_B1") (pin "29") (pinfunction "VREF_PREAMP_29") (pintype "bidirectional"))
    )
    (net (code "73") (name "VRST_PK_TEST_B") (class "Default")
      (node (ref "DUT_B1") (pin "55") (pinfunction "VRST_PK_TEST_55") (pintype "input"))
    )
    (net (code "74") (name "unconnected-(DUT_B1-NC-Pad16)") (class "Default")
      (node (ref "DUT_B1") (pin "16") (pinfunction "NC_16") (pintype "passive"))
    )
    (net (code "75") (name "unconnected-(DUT_B1-NC-Pad19)") (class "Default")
      (node (ref "DUT_B1") (pin "19") (pinfunction "NC_19") (pintype "passive"))
    )
    (net (code "76") (name "unconnected-(DUT_B1-NC-Pad21)") (class "Default")
      (node (ref "DUT_B1") (pin "21") (pinfunction "NC_21") (pintype "passive"))
    )
    (net (code "77") (name "unconnected-(DUT_B1-NC-Pad24)") (class "Default")
      (node (ref "DUT_B1") (pin "24") (pinfunction "NC_24") (pintype "passive"))
    )
    (net (code "78") (name "unconnected-(DUT_B1-NC-Pad27)") (class "Default")
      (node (ref "DUT_B1") (pin "27") (pinfunction "NC_27") (pintype "passive"))
    )
    (net (code "79") (name "unconnected-(DUT_B1-NC-Pad31)") (class "Default")
      (node (ref "DUT_B1") (pin "31") (pinfunction "NC_31") (pintype "passive"))
    )
    (net (code "80") (name "unconnected-(DUT_B1-NC-Pad33)") (class "Default")
      (node (ref "DUT_B1") (pin "33") (pinfunction "NC_33") (pintype "passive"))
    )
    (net (code "81") (name "unconnected-(DUT_B1-NC-Pad37)") (class "Default")
      (node (ref "DUT_B1") (pin "37") (pinfunction "NC_37") (pintype "passive"))
    )
    (net (code "82") (name "unconnected-(DUT_B1-NC-Pad39)") (class "Default")
      (node (ref "DUT_B1") (pin "39") (pinfunction "NC_39") (pintype "passive"))
    )
    (net (code "83") (name "unconnected-(DUT_B1-NC-Pad42)") (class "Default")
      (node (ref "DUT_B1") (pin "42") (pinfunction "NC_42") (pintype "passive"))
    )
    (net (code "84") (name "unconnected-(DUT_B1-NC-Pad48)") (class "Default")
      (node (ref "DUT_B1") (pin "48") (pinfunction "NC_48") (pintype "passive"))
    )
    (net (code "85") (name "unconnected-(IC14-NC-Pad6)") (class "Default")
      (node (ref "IC14") (pin "6") (pinfunction "NC_6") (pintype "passive"))
    )
    (net (code "86") (name "unconnected-(IC15-NC-Pad6)") (class "Default")
      (node (ref "IC15") (pin "6") (pinfunction "NC_6") (pintype "passive"))
    )
    (net (code "87") (name "unconnected-(IC16-~{Q}-Pad3)") (class "Default")
      (node (ref "IC16") (pin "3") (pinfunction "~{Q}_3") (pintype "passive"))
    )
    (net (code "88") (name "unconnected-(IC18-~{Q}-Pad3)") (class "Default")
      (node (ref "IC18") (pin "3") (pinfunction "~{Q}_3") (pintype "passive"))
    )
    (net (code "89") (name "unconnected-(IC19-~{Q}-Pad3)") (class "Default")
      (node (ref "IC19") (pin "3") (pinfunction "~{Q}_3") (pintype "passive"))
    )
    (net (code "90") (name "unconnected-(IC20-~{Q}-Pad3)") (class "Default")
      (node (ref "IC20") (pin "3") (pinfunction "~{Q}_3") (pintype "passive"))
    )
    (net (code "91") (name "unconnected-(IC21-~{Q}-Pad3)") (class "Default")
      (node (ref "IC21") (pin "3") (pinfunction "~{Q}_3") (pintype "passive"))
    )
    (net (code "92") (name "unconnected-(IC22-~{Q}-Pad3)") (class "Default")
      (node (ref "IC22") (pin "3") (pinfunction "~{Q}_3") (pintype "passive"))
    )
  )
)
